# untitled.net
KiCad netlist of a schematic drawn in EAGLE
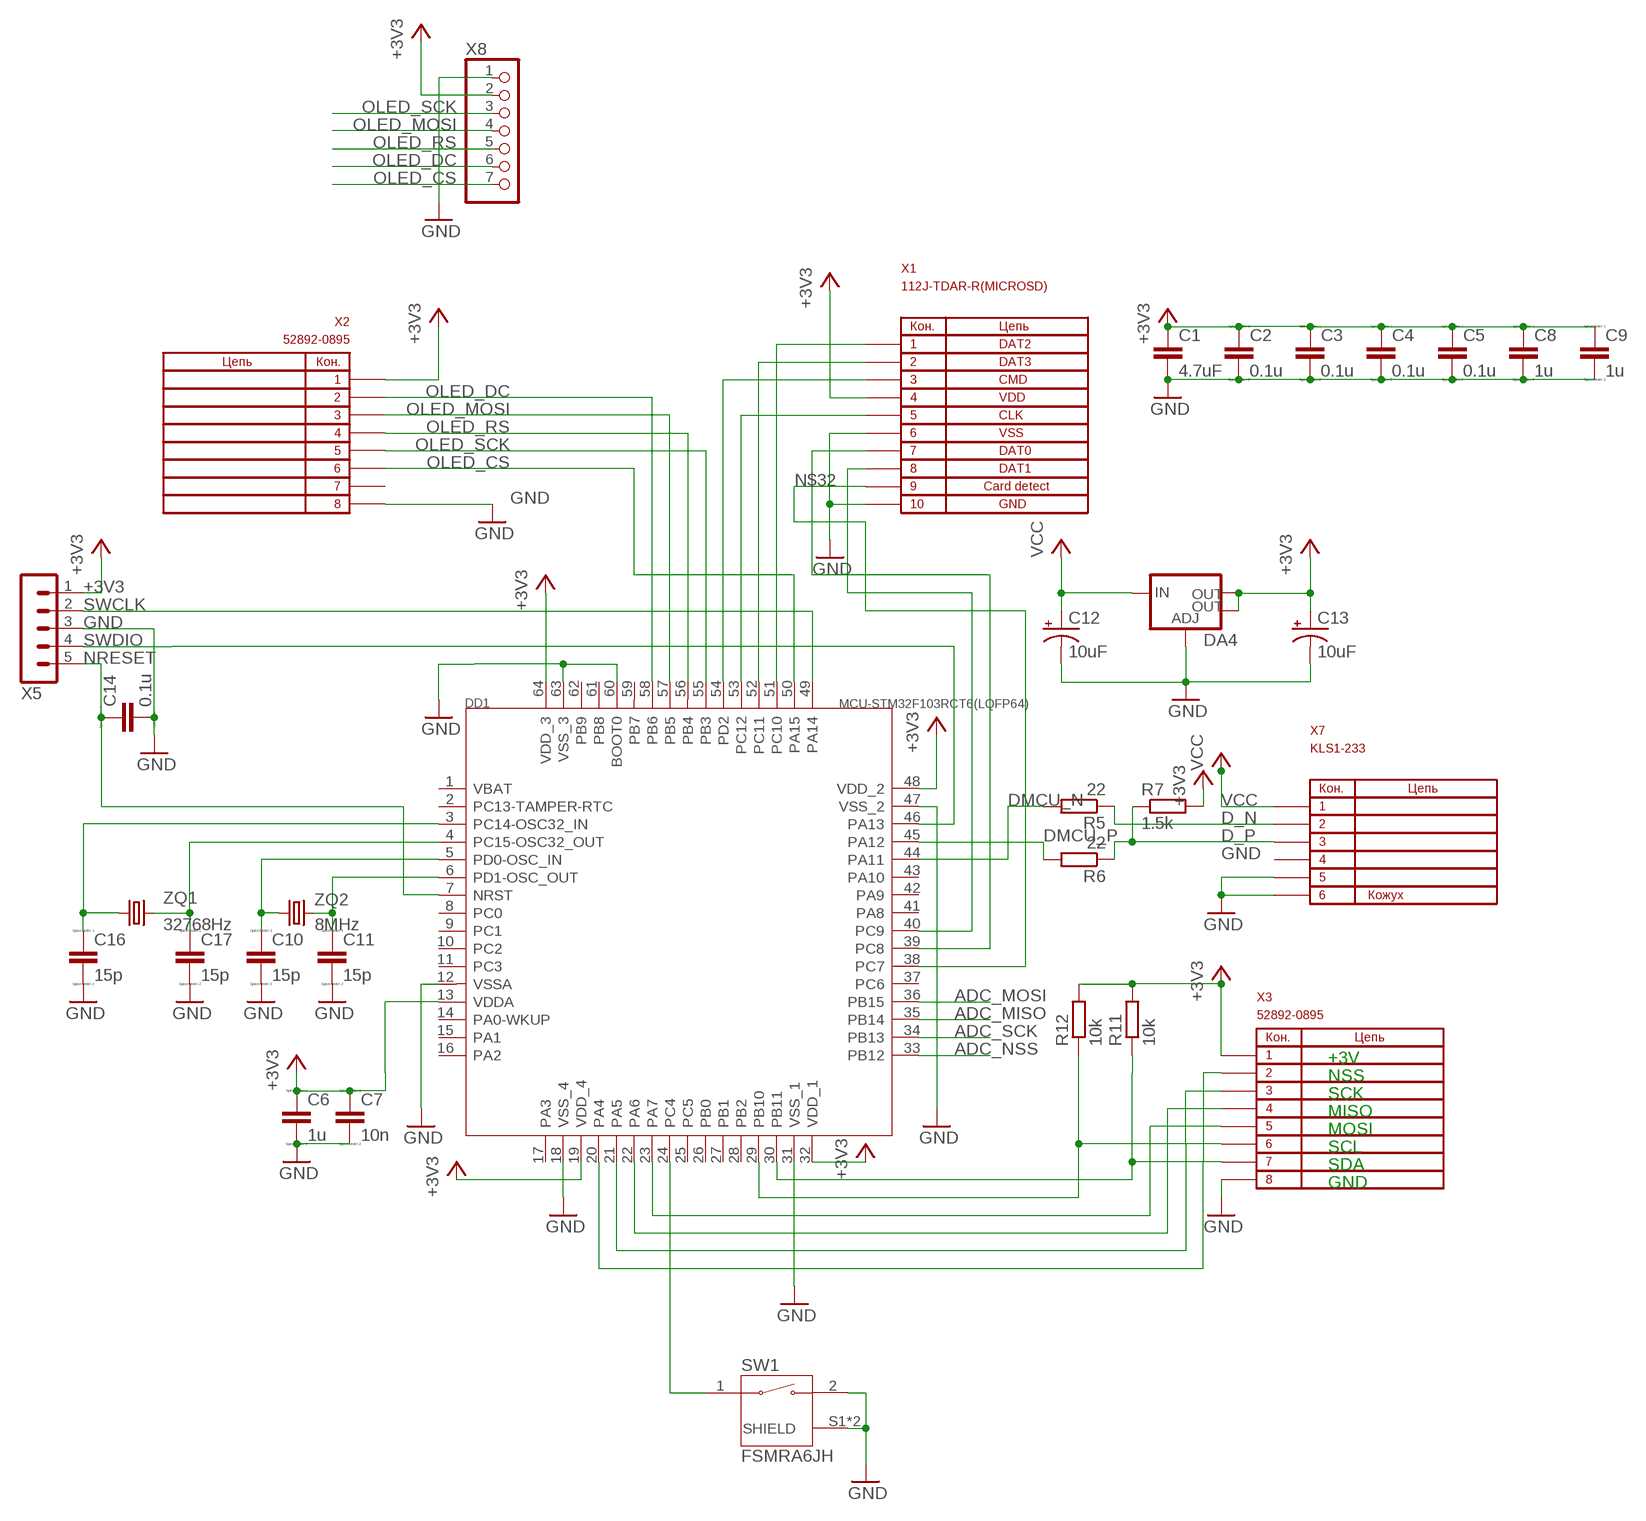
[diagram p0: schematic, sheet 1]
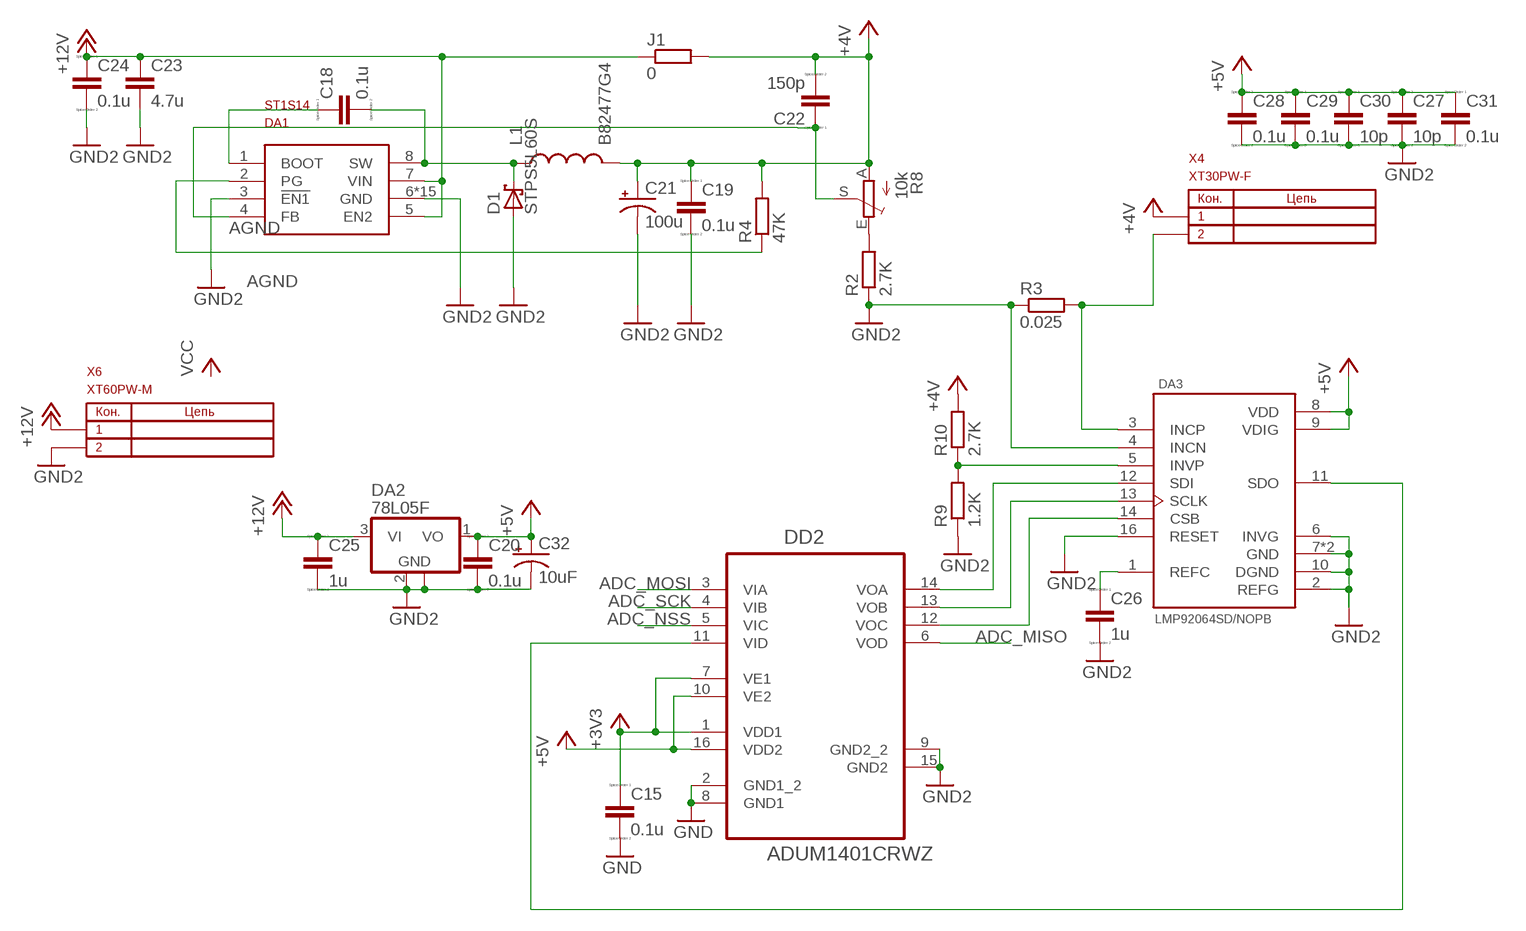
[diagram p1: schematic, sheet 2]

(export (version "E")
  (design (tool "Eeschema 10.0.6"))
  (components
    (comp (ref "C1")
      (value "4.7uF")
      (footprint "eagle-import:0603")
      (libsource (lib "eagle-import") (part "4.7UF0603"))
    )
    (comp (ref "C2")
      (value "0.1u")
      (footprint "eagle-import:C0603")
      (libsource (lib "eagle-import") (part "CC0603"))
    )
    (comp (ref "C3")
      (value "0.1u")
      (footprint "eagle-import:C0603")
      (libsource (lib "eagle-import") (part "CC0603"))
    )
    (comp (ref "C4")
      (value "0.1u")
      (footprint "eagle-import:C0603")
      (libsource (lib "eagle-import") (part "CC0603"))
    )
    (comp (ref "C5")
      (value "0.1u")
      (footprint "eagle-import:C0603")
      (libsource (lib "eagle-import") (part "CC0603"))
    )
    (comp (ref "C6")
      (value "1u")
      (footprint "eagle-import:C0603")
      (libsource (lib "eagle-import") (part "CC0603"))
    )
    (comp (ref "C7")
      (value "10n")
      (footprint "eagle-import:C0603")
      (libsource (lib "eagle-import") (part "CC0603"))
    )
    (comp (ref "C8")
      (value "1u")
      (footprint "eagle-import:C0603")
      (libsource (lib "eagle-import") (part "CC0603"))
    )
    (comp (ref "C9")
      (value "1u")
      (footprint "eagle-import:C0603")
      (libsource (lib "eagle-import") (part "CC0603"))
    )
    (comp (ref "C10")
      (value "15p")
      (footprint "eagle-import:C0603")
      (libsource (lib "eagle-import") (part "CC0603"))
    )
    (comp (ref "C11")
      (value "15p")
      (footprint "eagle-import:C0603")
      (libsource (lib "eagle-import") (part "CC0603"))
    )
    (comp (ref "C12")
      (value "10uF")
      (footprint "eagle-import:EIA3216")
      (libsource (lib "eagle-import") (part "10UF-POLAR-EIA3216-16V-10%(TANT)"))
    )
    (comp (ref "C13")
      (value "10uF")
      (footprint "eagle-import:EIA3216")
      (libsource (lib "eagle-import") (part "10UF-POLAR-EIA3216-16V-10%(TANT)"))
    )
    (comp (ref "C14")
      (value "0.1u")
      (footprint "eagle-import:C0603")
      (libsource (lib "eagle-import") (part "CC0603"))
    )
    (comp (ref "C16")
      (value "15p")
      (footprint "eagle-import:C0603")
      (libsource (lib "eagle-import") (part "CC0603"))
    )
    (comp (ref "C17")
      (value "15p")
      (footprint "eagle-import:C0603")
      (libsource (lib "eagle-import") (part "CC0603"))
    )
    (comp (ref "DA4")
      (value "V_REG_LM1117SOT223")
      (footprint "eagle-import:SOT223")
      (libsource (lib "eagle-import") (part "V_REG_LM1117SOT223"))
    )
    (comp (ref "DD1")
      (value "MCU-STM32F103RCT6(LQFP64)")
      (footprint "eagle-import:LQFP64-0.5-10X10MM")
      (fields (field (name "MF") "STMicroelectronics") (field (name "MP") "STM32F103RCT6"))
      (libsource (lib "eagle-import") (part "MCU-STM32F103RCT6(LQFP64)"))
    )
    (comp (ref "R5")
      (value "22")
      (footprint "eagle-import:R0603")
      (libsource (lib "eagle-import") (part "resistor_348_R-EU_R0603"))
    )
    (comp (ref "R6")
      (value "22")
      (footprint "eagle-import:R0603")
      (libsource (lib "eagle-import") (part "resistor_348_R-EU_R0603"))
    )
    (comp (ref "R7")
      (value "1.5k")
      (footprint "eagle-import:R0603")
      (libsource (lib "eagle-import") (part "resistor_348_R-EU_R0603"))
    )
    (comp (ref "R11")
      (value "10k")
      (footprint "eagle-import:R0603")
      (libsource (lib "eagle-import") (part "resistor_348_R-EU_R0603"))
    )
    (comp (ref "R12")
      (value "10k")
      (footprint "eagle-import:R0603")
      (libsource (lib "eagle-import") (part "resistor_348_R-EU_R0603"))
    )
    (comp (ref "SW1")
      (value "FSMRA6JH")
      (footprint "eagle-import:TE_FSMRA6JH")
      (fields (field (name "MF") "TE Connectivity"))
      (libsource (lib "eagle-import") (part "FSMRA6JH"))
    )
    (comp (ref "X1")
      (value "112J-TDAR-R(MICROSD)")
      (footprint "eagle-import:112J-TDAR-R")
      (libsource (lib "eagle-import") (part "112J-TDAR-R(MICROSD)"))
    )
    (comp (ref "X2")
      (value "52892-0895")
      (footprint "eagle-import:MOLEX_52892-0895")
      (fields (field (name "MF") "Molex"))
      (libsource (lib "eagle-import") (part "52892-0895"))
    )
    (comp (ref "X3")
      (value "52892-0895")
      (footprint "eagle-import:MOLEX_52892-0895")
      (fields (field (name "MF") "Molex"))
      (libsource (lib "eagle-import") (part "52892-0895"))
    )
    (comp (ref "X5")
      (value "MA05-1")
      (footprint "eagle-import:MA05-1")
      (libsource (lib "eagle-import") (part "MA05-1"))
    )
    (comp (ref "X7")
      (value "KLS1-233")
      (footprint "eagle-import:KLS1-233")
      (libsource (lib "eagle-import") (part "KLS1-233"))
    )
    (comp (ref "X8")
      (value "PINHD-1X7")
      (footprint "eagle-import:1X07")
      (libsource (lib "eagle-import") (part "PINHD-1X7"))
    )
    (comp (ref "ZQ1")
      (value "32768Hz")
      (footprint "eagle-import:3.2X1.5")
      (libsource (lib "eagle-import") (part "KX-327-NHT"))
    )
    (comp (ref "ZQ2")
      (value "8MHz")
      (footprint "eagle-import:HC49UP")
      (libsource (lib "eagle-import") (part "CRYSTALHC49UP"))
    )
    (comp (ref "C15")
      (value "0.1u")
      (footprint "eagle-import:C0603")
      (libsource (lib "eagle-import") (part "CC0603"))
    )
    (comp (ref "C18")
      (value "0.1u")
      (footprint "eagle-import:C0603")
      (libsource (lib "eagle-import") (part "CC0603"))
    )
    (comp (ref "C19")
      (value "0.1u")
      (footprint "eagle-import:C0603")
      (libsource (lib "eagle-import") (part "CC0603"))
    )
    (comp (ref "C20")
      (value "0.1u")
      (footprint "eagle-import:C0603")
      (libsource (lib "eagle-import") (part "CC0603"))
    )
    (comp (ref "C21")
      (value "100u")
      (footprint "eagle-import:150CLZ-1014")
      (libsource (lib "eagle-import") (part "CPOL-US150CLZ-1014"))
    )
    (comp (ref "C22")
      (value "150p")
      (footprint "eagle-import:C0603")
      (libsource (lib "eagle-import") (part "CC0603"))
    )
    (comp (ref "C23")
      (value "4.7u")
      (footprint "eagle-import:C2220K")
      (libsource (lib "eagle-import") (part "C-EUC2220K"))
    )
    (comp (ref "C24")
      (value "0.1u")
      (footprint "eagle-import:C0603")
      (libsource (lib "eagle-import") (part "CC0603"))
    )
    (comp (ref "C25")
      (value "1u")
      (footprint "eagle-import:C1206")
      (libsource (lib "eagle-import") (part "CC1206"))
    )
    (comp (ref "C26")
      (value "1u")
      (footprint "eagle-import:C0603")
      (libsource (lib "eagle-import") (part "CC0603"))
    )
    (comp (ref "C27")
      (value "10p")
      (footprint "eagle-import:C0603")
      (libsource (lib "eagle-import") (part "CC0603"))
    )
    (comp (ref "C28")
      (value "0.1u")
      (footprint "eagle-import:C0603")
      (libsource (lib "eagle-import") (part "CC0603"))
    )
    (comp (ref "C29")
      (value "0.1u")
      (footprint "eagle-import:C0603")
      (libsource (lib "eagle-import") (part "CC0603"))
    )
    (comp (ref "C30")
      (value "10p")
      (footprint "eagle-import:C0603")
      (libsource (lib "eagle-import") (part "CC0603"))
    )
    (comp (ref "C31")
      (value "0.1u")
      (footprint "eagle-import:C0603")
      (libsource (lib "eagle-import") (part "CC0603"))
    )
    (comp (ref "C32")
      (value "10uF")
      (footprint "eagle-import:EIA3216")
      (libsource (lib "eagle-import") (part "10UF-POLAR-EIA3216-16V-10%(TANT)"))
    )
    (comp (ref "D1")
      (value "STPS5L60S")
      (footprint "eagle-import:SMC")
      (libsource (lib "eagle-import") (part "STPS5L60S"))
    )
    (comp (ref "DA1")
      (value "ST1S14")
      (footprint "eagle-import:HSOP8")
      (libsource (lib "eagle-import") (part "ST1S14"))
    )
    (comp (ref "DA2")
      (value "78L05F")
      (footprint "eagle-import:SOT89")
      (libsource (lib "eagle-import") (part "78LF05"))
    )
    (comp (ref "DA3")
      (value "LMP92064SD/NOPB")
      (footprint "eagle-import:SON50P400X500X80-17N")
      (fields (field (name "MF") "Texas Instruments"))
      (libsource (lib "eagle-import") (part "LMP92064SD/NOPB"))
    )
    (comp (ref "DD2")
      (value "ADUM1401CRWZ")
      (footprint "eagle-import:SO-16W")
      (fields (field (name "MF") "Analog Devices"))
      (libsource (lib "eagle-import") (part "ADUM1401CRWZ"))
    )
    (comp (ref "J1")
      (value "0")
      (footprint "eagle-import:R2010")
      (libsource (lib "eagle-import") (part "R-EU_R2010"))
    )
    (comp (ref "L1")
      (value "B82477G4")
      (footprint "eagle-import:B82477G4")
      (libsource (lib "eagle-import") (part "B82477G4"))
    )
    (comp (ref "R2")
      (value "2.7K")
      (footprint "eagle-import:R0603")
      (libsource (lib "eagle-import") (part "resistor_348_R-EU_R0603"))
    )
    (comp (ref "R3")
      (value "0.025")
      (footprint "eagle-import:R2010")
      (libsource (lib "eagle-import") (part "R-EU_R2010"))
    )
    (comp (ref "R4")
      (value "47K")
      (footprint "eagle-import:R0603")
      (libsource (lib "eagle-import") (part "resistor_348_R-EU_R0603"))
    )
    (comp (ref "R8")
      (value "10k")
      (footprint "eagle-import:CA6V")
      (libsource (lib "eagle-import") (part "TRIM_EU-CA6V"))
    )
    (comp (ref "R9")
      (value "1.2K")
      (footprint "eagle-import:R0603")
      (libsource (lib "eagle-import") (part "resistor_348_R-EU_R0603"))
    )
    (comp (ref "R10")
      (value "2.7K")
      (footprint "eagle-import:R0603")
      (libsource (lib "eagle-import") (part "resistor_348_R-EU_R0603"))
    )
    (comp (ref "X4")
      (value "XT30PW-F")
      (footprint "eagle-import:XT30PW-F")
      (libsource (lib "eagle-import") (part "XT30PW-F"))
    )
    (comp (ref "X6")
      (value "XT60PW-M")
      (footprint "eagle-import:XT60PW-M")
      (libsource (lib "eagle-import") (part "XT60PW-M"))
    )
  )
  (nets
    (net (code "1") (name "+3V3") (class "Default")
      (node (ref "C1") (pin "1") (pinfunction "1_1") (pintype "passive"))
      (node (ref "C13") (pin "+") (pinfunction "+_+") (pintype "passive"))
      (node (ref "C15") (pin "1") (pinfunction "1_1") (pintype "passive"))
      (node (ref "C2") (pin "1") (pinfunction "1_1") (pintype "passive"))
      (node (ref "C3") (pin "1") (pinfunction "1_1") (pintype "passive"))
      (node (ref "C4") (pin "1") (pinfunction "1_1") (pintype "passive"))
      (node (ref "C5") (pin "1") (pinfunction "1_1") (pintype "passive"))
      (node (ref "C6") (pin "1") (pinfunction "1_1") (pintype "passive"))
      (node (ref "C7") (pin "1") (pinfunction "1_1") (pintype "passive"))
      (node (ref "C8") (pin "1") (pinfunction "1_1") (pintype "passive"))
      (node (ref "C9") (pin "1") (pinfunction "1_1") (pintype "passive"))
      (node (ref "DA4") (pin "2") (pinfunction "OUT_2") (pintype "output"))
      (node (ref "DA4") (pin "4") (pinfunction "OUT_4") (pintype "output"))
      (node (ref "DD1") (pin "13") (pinfunction "VDDA_13") (pintype "bidirectional"))
      (node (ref "DD1") (pin "19") (pinfunction "VDD_4_19") (pintype "bidirectional"))
      (node (ref "DD1") (pin "32") (pinfunction "VDD_1_32") (pintype "bidirectional"))
      (node (ref "DD1") (pin "48") (pinfunction "VDD_2_48") (pintype "bidirectional"))
      (node (ref "DD1") (pin "64") (pinfunction "VDD_3_64") (pintype "bidirectional"))
      (node (ref "DD2") (pin "1") (pinfunction "VDD1_1") (pintype "power_in"))
      (node (ref "DD2") (pin "7") (pinfunction "VE1_7") (pintype "passive"))
      (node (ref "R11") (pin "2") (pinfunction "2_2") (pintype "passive"))
      (node (ref "R12") (pin "2") (pinfunction "2_2") (pintype "passive"))
      (node (ref "R7") (pin "2") (pinfunction "2_2") (pintype "passive"))
      (node (ref "X1") (pin "P$4") (pinfunction "P$4_P$4") (pintype "bidirectional"))
      (node (ref "X2") (pin "1") (pinfunction "P$1_1") (pintype "bidirectional"))
      (node (ref "X3") (pin "1") (pinfunction "P$1_1") (pintype "bidirectional"))
      (node (ref "X5") (pin "1") (pinfunction "1_1") (pintype "passive"))
      (node (ref "X8") (pin "2") (pinfunction "2_2") (pintype "passive"))
    )
    (net (code "2") (name "+4V") (class "Default")
      (node (ref "C19") (pin "1") (pinfunction "1_1") (pintype "passive"))
      (node (ref "C21") (pin "+") (pinfunction "+_+") (pintype "passive"))
      (node (ref "C22") (pin "2") (pinfunction "2_2") (pintype "passive"))
      (node (ref "J1") (pin "2") (pinfunction "2_2") (pintype "passive"))
      (node (ref "L1") (pin "P$2") (pinfunction "2_P$2") (pintype "passive"))
      (node (ref "R10") (pin "2") (pinfunction "2_2") (pintype "passive"))
      (node (ref "R4") (pin "2") (pinfunction "2_2") (pintype "passive"))
      (node (ref "R8") (pin "A") (pinfunction "A_A") (pintype "passive"))
      (node (ref "X4") (pin "P$2") (pinfunction "P$1_P$2") (pintype "bidirectional"))
    )
    (net (code "3") (name "+5V") (class "Default")
      (node (ref "C20") (pin "1") (pinfunction "1_1") (pintype "passive"))
      (node (ref "C27") (pin "1") (pinfunction "1_1") (pintype "passive"))
      (node (ref "C28") (pin "1") (pinfunction "1_1") (pintype "passive"))
      (node (ref "C29") (pin "1") (pinfunction "1_1") (pintype "passive"))
      (node (ref "C30") (pin "1") (pinfunction "1_1") (pintype "passive"))
      (node (ref "C31") (pin "1") (pinfunction "1_1") (pintype "passive"))
      (node (ref "C32") (pin "+") (pinfunction "+_+") (pintype "passive"))
      (node (ref "DA2") (pin "1") (pinfunction "VO_1") (pintype "passive"))
      (node (ref "DA3") (pin "8") (pinfunction "VDD_8") (pintype "power_in"))
      (node (ref "DA3") (pin "9") (pinfunction "VDIG_9") (pintype "power_in"))
      (node (ref "DD2") (pin "10") (pinfunction "VE2_10") (pintype "passive"))
      (node (ref "DD2") (pin "16") (pinfunction "VDD2_16") (pintype "power_in"))
    )
    (net (code "4") (name "+12V") (class "Default")
      (node (ref "C23") (pin "1") (pinfunction "1_1") (pintype "passive"))
      (node (ref "C24") (pin "1") (pinfunction "1_1") (pintype "passive"))
      (node (ref "C25") (pin "1") (pinfunction "1_1") (pintype "passive"))
      (node (ref "DA1") (pin "5") (pinfunction "EN2_5") (pintype "bidirectional"))
      (node (ref "DA1") (pin "7") (pinfunction "VIN_7") (pintype "bidirectional"))
      (node (ref "DA2") (pin "3") (pinfunction "VI_3") (pintype "input"))
      (node (ref "J1") (pin "1") (pinfunction "1_1") (pintype "passive"))
      (node (ref "X6") (pin "P$2") (pinfunction "P$1_P$2") (pintype "bidirectional"))
    )
    (net (code "5") (name "ADC_MISO") (class "Default")
      (node (ref "DD1") (pin "35") (pinfunction "PB14_35") (pintype "bidirectional"))
      (node (ref "DD2") (pin "6") (pinfunction "VOD_6") (pintype "passive"))
    )
    (net (code "6") (name "ADC_MOSI") (class "Default")
      (node (ref "DD1") (pin "36") (pinfunction "PB15_36") (pintype "bidirectional"))
      (node (ref "DD2") (pin "3") (pinfunction "VIA_3") (pintype "passive"))
    )
    (net (code "7") (name "ADC_NSS") (class "Default")
      (node (ref "DD1") (pin "33") (pinfunction "PB12_33") (pintype "bidirectional"))
      (node (ref "DD2") (pin "5") (pinfunction "VIC_5") (pintype "passive"))
    )
    (net (code "8") (name "ADC_SCK") (class "Default")
      (node (ref "DD1") (pin "34") (pinfunction "PB13_34") (pintype "bidirectional"))
      (node (ref "DD2") (pin "4") (pinfunction "VIB_4") (pintype "passive"))
    )
    (net (code "9") (name "AGND") (class "Default")
      (node (ref "C19") (pin "2") (pinfunction "2_2") (pintype "passive"))
      (node (ref "C20") (pin "2") (pinfunction "2_2") (pintype "passive"))
      (node (ref "C21") (pin "-") (pinfunction "-_-") (pintype "passive"))
      (node (ref "C23") (pin "2") (pinfunction "2_2") (pintype "passive"))
      (node (ref "C24") (pin "2") (pinfunction "2_2") (pintype "passive"))
      (node (ref "C25") (pin "2") (pinfunction "2_2") (pintype "passive"))
      (node (ref "C26") (pin "2") (pinfunction "2_2") (pintype "passive"))
      (node (ref "C27") (pin "2") (pinfunction "2_2") (pintype "passive"))
      (node (ref "C28") (pin "2") (pinfunction "2_2") (pintype "passive"))
      (node (ref "C29") (pin "2") (pinfunction "2_2") (pintype "passive"))
      (node (ref "C30") (pin "2") (pinfunction "2_2") (pintype "passive"))
      (node (ref "C31") (pin "2") (pinfunction "2_2") (pintype "passive"))
      (node (ref "C32") (pin "-") (pinfunction "-_-") (pintype "passive"))
      (node (ref "D1") (pin "A") (pinfunction "A_A") (pintype "passive"))
      (node (ref "DA1") (pin "3") (pinfunction "~{EN1}_3") (pintype "bidirectional"))
      (node (ref "DA1") (pin "6") (pinfunction "GND_6") (pintype "bidirectional"))
      (node (ref "DA1") (pin "P$10") (pinfunction "GND_P$10") (pintype "bidirectional"))
      (node (ref "DA1") (pin "P$11") (pinfunction "GND_P$11") (pintype "bidirectional"))
      (node (ref "DA1") (pin "P$12") (pinfunction "GND_P$12") (pintype "bidirectional"))
      (node (ref "DA1") (pin "P$13") (pinfunction "GND_P$13") (pintype "bidirectional"))
      (node (ref "DA1") (pin "P$14") (pinfunction "GND_P$14") (pintype "bidirectional"))
      (node (ref "DA1") (pin "P$15") (pinfunction "GND_P$15") (pintype "bidirectional"))
      (node (ref "DA1") (pin "P$16") (pinfunction "GND_P$16") (pintype "bidirectional"))
      (node (ref "DA1") (pin "P$17") (pinfunction "GND_P$17") (pintype "bidirectional"))
      (node (ref "DA1") (pin "P$18") (pinfunction "GND_P$18") (pintype "bidirectional"))
      (node (ref "DA1") (pin "P$19") (pinfunction "GND_P$19") (pintype "bidirectional"))
      (node (ref "DA1") (pin "P$20") (pinfunction "GND_P$20") (pintype "bidirectional"))
      (node (ref "DA1") (pin "P$21") (pinfunction "GND_P$21") (pintype "bidirectional"))
      (node (ref "DA1") (pin "P$22") (pinfunction "GND_P$22") (pintype "bidirectional"))
      (node (ref "DA1") (pin "P$9") (pinfunction "GND_P$9") (pintype "bidirectional"))
      (node (ref "DA2") (pin "2") (pinfunction "GND_2") (pintype "passive"))
      (node (ref "DA2") (pin "2@1") (pinfunction "GND_2@1") (pintype "passive"))
      (node (ref "DA3") (pin "10") (pinfunction "DGND_10") (pintype "power_in"))
      (node (ref "DA3") (pin "16") (pinfunction "RESET_16") (pintype "input"))
      (node (ref "DA3") (pin "17") (pinfunction "GND_17") (pintype "power_in"))
      (node (ref "DA3") (pin "2") (pinfunction "REFG_2") (pintype "power_in"))
      (node (ref "DA3") (pin "4") (pinfunction "INCN_4") (pintype "input"))
      (node (ref "DA3") (pin "6") (pinfunction "INVG_6") (pintype "power_in"))
      (node (ref "DA3") (pin "7") (pinfunction "GND_7") (pintype "power_in"))
      (node (ref "DD2") (pin "15") (pinfunction "GND2_15") (pintype "passive"))
      (node (ref "DD2") (pin "9") (pinfunction "GND2_2_9") (pintype "passive"))
      (node (ref "R2") (pin "1") (pinfunction "1_1") (pintype "passive"))
      (node (ref "R3") (pin "1") (pinfunction "1_1") (pintype "passive"))
      (node (ref "R9") (pin "1") (pinfunction "1_1") (pintype "passive"))
      (node (ref "X6") (pin "P$1") (pinfunction "P$2_P$1") (pintype "bidirectional"))
    )
    (net (code "10") (name "DMCU_N") (class "Default")
      (node (ref "DD1") (pin "44") (pinfunction "PA11_44") (pintype "bidirectional"))
      (node (ref "R5") (pin "2") (pinfunction "2_2") (pintype "passive"))
    )
    (net (code "11") (name "DMCU_P") (class "Default")
      (node (ref "DD1") (pin "45") (pinfunction "PA12_45") (pintype "bidirectional"))
      (node (ref "R6") (pin "2") (pinfunction "2_2") (pintype "passive"))
    )
    (net (code "12") (name "D_N") (class "Default")
      (node (ref "R5") (pin "1") (pinfunction "1_1") (pintype "passive"))
      (node (ref "X7") (pin "2") (pinfunction "P$2_2") (pintype "bidirectional"))
    )
    (net (code "13") (name "D_P") (class "Default")
      (node (ref "R6") (pin "1") (pinfunction "1_1") (pintype "passive"))
      (node (ref "R7") (pin "1") (pinfunction "1_1") (pintype "passive"))
      (node (ref "X7") (pin "3") (pinfunction "P$3_3") (pintype "bidirectional"))
    )
    (net (code "14") (name "GND") (class "Default")
      (node (ref "C1") (pin "2") (pinfunction "2_2") (pintype "passive"))
      (node (ref "C10") (pin "2") (pinfunction "2_2") (pintype "passive"))
      (node (ref "C11") (pin "2") (pinfunction "2_2") (pintype "passive"))
      (node (ref "C12") (pin "-") (pinfunction "-_-") (pintype "passive"))
      (node (ref "C13") (pin "-") (pinfunction "-_-") (pintype "passive"))
      (node (ref "C14") (pin "2") (pinfunction "2_2") (pintype "passive"))
      (node (ref "C15") (pin "2") (pinfunction "2_2") (pintype "passive"))
      (node (ref "C16") (pin "2") (pinfunction "2_2") (pintype "passive"))
      (node (ref "C17") (pin "2") (pinfunction "2_2") (pintype "passive"))
      (node (ref "C2") (pin "2") (pinfunction "2_2") (pintype "passive"))
      (node (ref "C3") (pin "2") (pinfunction "2_2") (pintype "passive"))
      (node (ref "C4") (pin "2") (pinfunction "2_2") (pintype "passive"))
      (node (ref "C5") (pin "2") (pinfunction "2_2") (pintype "passive"))
      (node (ref "C6") (pin "2") (pinfunction "2_2") (pintype "passive"))
      (node (ref "C7") (pin "2") (pinfunction "2_2") (pintype "passive"))
      (node (ref "C8") (pin "2") (pinfunction "2_2") (pintype "passive"))
      (node (ref "C9") (pin "2") (pinfunction "2_2") (pintype "passive"))
      (node (ref "DA4") (pin "1") (pinfunction "ADJ_1") (pintype "input"))
      (node (ref "DD1") (pin "12") (pinfunction "VSSA_12") (pintype "bidirectional"))
      (node (ref "DD1") (pin "18") (pinfunction "VSS_4_18") (pintype "bidirectional"))
      (node (ref "DD1") (pin "31") (pinfunction "VSS_1_31") (pintype "bidirectional"))
      (node (ref "DD1") (pin "47") (pinfunction "VSS_2_47") (pintype "bidirectional"))
      (node (ref "DD1") (pin "60") (pinfunction "BOOT0_60") (pintype "bidirectional"))
      (node (ref "DD1") (pin "63") (pinfunction "VSS_3_63") (pintype "bidirectional"))
      (node (ref "DD2") (pin "2") (pinfunction "GND1_2_2") (pintype "passive"))
      (node (ref "DD2") (pin "8") (pinfunction "GND1_8") (pintype "passive"))
      (node (ref "SW1") (pin "2") (pinfunction "2_2") (pintype "passive"))
      (node (ref "SW1") (pin "S1") (pinfunction "SHIELD_S1") (pintype "passive"))
      (node (ref "SW1") (pin "S2") (pinfunction "SHIELD_S2") (pintype "passive"))
      (node (ref "X1") (pin "P$10") (pinfunction "P$10_P$10") (pintype "bidirectional"))
      (node (ref "X1") (pin "P$11") (pinfunction "P$10_P$11") (pintype "bidirectional"))
      (node (ref "X1") (pin "P$12") (pinfunction "P$10_P$12") (pintype "bidirectional"))
      (node (ref "X1") (pin "P$13") (pinfunction "P$10_P$13") (pintype "bidirectional"))
      (node (ref "X1") (pin "P$6") (pinfunction "P$6_P$6") (pintype "bidirectional"))
      (node (ref "X2") (pin "8") (pinfunction "P$8_8") (pintype "bidirectional"))
      (node (ref "X3") (pin "8") (pinfunction "P$8_8") (pintype "bidirectional"))
      (node (ref "X5") (pin "3") (pinfunction "3_3") (pintype "passive"))
      (node (ref "X7") (pin "5") (pinfunction "P$5_5") (pintype "bidirectional"))
      (node (ref "X7") (pin "SH4") (pinfunction "P$6_SH4") (pintype "bidirectional"))
      (node (ref "X7") (pin "SH5") (pinfunction "P$6_SH5") (pintype "bidirectional"))
      (node (ref "X7") (pin "SH6") (pinfunction "P$6_SH6") (pintype "bidirectional"))
      (node (ref "X7") (pin "SH7") (pinfunction "P$6_SH7") (pintype "bidirectional"))
      (node (ref "X8") (pin "1") (pinfunction "1_1") (pintype "passive"))
    )
    (net (code "15") (name "N$32") (class "Default")
      (node (ref "DD1") (pin "38") (pinfunction "PC7_38") (pintype "bidirectional"))
      (node (ref "X1") (pin "P$9") (pinfunction "P$9_P$9") (pintype "bidirectional"))
    )
    (net (code "16") (name "NRESET") (class "Default")
      (node (ref "C14") (pin "1") (pinfunction "1_1") (pintype "passive"))
      (node (ref "DD1") (pin "7") (pinfunction "NRST_7") (pintype "bidirectional"))
      (node (ref "X5") (pin "5") (pinfunction "5_5") (pintype "passive"))
    )
    (net (code "17") (name "Net-(DA1-BOOT)") (class "Default")
      (node (ref "C18") (pin "1") (pinfunction "1_1") (pintype "passive"))
      (node (ref "DA1") (pin "1") (pinfunction "BOOT_1") (pintype "bidirectional"))
    )
    (net (code "18") (name "Net-(DA1-FB)") (class "Default")
      (node (ref "C22") (pin "1") (pinfunction "1_1") (pintype "passive"))
      (node (ref "DA1") (pin "4") (pinfunction "FB_4") (pintype "bidirectional"))
      (node (ref "R8") (pin "S") (pinfunction "S_S") (pintype "passive"))
    )
    (net (code "19") (name "Net-(DA1-PG)") (class "Default")
      (node (ref "DA1") (pin "2") (pinfunction "PG_2") (pintype "bidirectional"))
      (node (ref "R4") (pin "1") (pinfunction "1_1") (pintype "passive"))
    )
    (net (code "20") (name "Net-(DA1-SW)") (class "Default")
      (node (ref "C18") (pin "2") (pinfunction "2_2") (pintype "passive"))
      (node (ref "D1") (pin "C") (pinfunction "C_C") (pintype "passive"))
      (node (ref "DA1") (pin "8") (pinfunction "SW_8") (pintype "bidirectional"))
      (node (ref "L1") (pin "P$1") (pinfunction "1_P$1") (pintype "passive"))
    )
    (net (code "21") (name "Net-(DA3-CSB)") (class "Default")
      (node (ref "DA3") (pin "14") (pinfunction "CSB_14") (pintype "input"))
      (node (ref "DD2") (pin "12") (pinfunction "VOC_12") (pintype "passive"))
    )
    (net (code "22") (name "Net-(DA3-INCP)") (class "Default")
      (node (ref "DA3") (pin "3") (pinfunction "INCP_3") (pintype "input"))
      (node (ref "R3") (pin "2") (pinfunction "2_2") (pintype "passive"))
      (node (ref "X4") (pin "P$1") (pinfunction "P$2_P$1") (pintype "bidirectional"))
    )
    (net (code "23") (name "Net-(DA3-INVP)") (class "Default")
      (node (ref "DA3") (pin "5") (pinfunction "INVP_5") (pintype "input"))
      (node (ref "R10") (pin "1") (pinfunction "1_1") (pintype "passive"))
      (node (ref "R9") (pin "2") (pinfunction "2_2") (pintype "passive"))
    )
    (net (code "24") (name "Net-(DA3-REFC)") (class "Default")
      (node (ref "C26") (pin "1") (pinfunction "1_1") (pintype "passive"))
      (node (ref "DA3") (pin "1") (pinfunction "REFC_1") (pintype "passive"))
    )
    (net (code "25") (name "Net-(DA3-SCLK)") (class "Default")
      (node (ref "DA3") (pin "13") (pinfunction "SCLK_13") (pintype "input"))
      (node (ref "DD2") (pin "13") (pinfunction "VOB_13") (pintype "passive"))
    )
    (net (code "26") (name "Net-(DA3-SDI)") (class "Default")
      (node (ref "DA3") (pin "12") (pinfunction "SDI_12") (pintype "input"))
      (node (ref "DD2") (pin "14") (pinfunction "VOA_14") (pintype "passive"))
    )
    (net (code "27") (name "Net-(DA3-SDO)") (class "Default")
      (node (ref "DA3") (pin "11") (pinfunction "SDO_11") (pintype "output"))
      (node (ref "DD2") (pin "11") (pinfunction "VID_11") (pintype "passive"))
    )
    (net (code "28") (name "Net-(DD1-PA4)") (class "Default")
      (node (ref "DD1") (pin "20") (pinfunction "PA4_20") (pintype "bidirectional"))
      (node (ref "X3") (pin "2") (pinfunction "P$2_2") (pintype "bidirectional"))
    )
    (net (code "29") (name "Net-(DD1-PA5)") (class "Default")
      (node (ref "DD1") (pin "21") (pinfunction "PA5_21") (pintype "bidirectional"))
      (node (ref "X3") (pin "3") (pinfunction "P$3_3") (pintype "bidirectional"))
    )
    (net (code "30") (name "Net-(DD1-PA6)") (class "Default")
      (node (ref "DD1") (pin "22") (pinfunction "PA6_22") (pintype "bidirectional"))
      (node (ref "X3") (pin "4") (pinfunction "P$4_4") (pintype "bidirectional"))
    )
    (net (code "31") (name "Net-(DD1-PA7)") (class "Default")
      (node (ref "DD1") (pin "23") (pinfunction "PA7_23") (pintype "bidirectional"))
      (node (ref "X3") (pin "5") (pinfunction "P$5_5") (pintype "bidirectional"))
    )
    (net (code "32") (name "Net-(DD1-PB10)") (class "Default")
      (node (ref "DD1") (pin "29") (pinfunction "PB10_29") (pintype "bidirectional"))
      (node (ref "R12") (pin "1") (pinfunction "1_1") (pintype "passive"))
      (node (ref "X3") (pin "6") (pinfunction "P$6_6") (pintype "bidirectional"))
    )
    (net (code "33") (name "Net-(DD1-PB11)") (class "Default")
      (node (ref "DD1") (pin "30") (pinfunction "PB11_30") (pintype "bidirectional"))
      (node (ref "R11") (pin "1") (pinfunction "1_1") (pintype "passive"))
      (node (ref "X3") (pin "7") (pinfunction "P$7_7") (pintype "bidirectional"))
    )
    (net (code "34") (name "Net-(DD1-PC4)") (class "Default")
      (node (ref "DD1") (pin "24") (pinfunction "PC4_24") (pintype "bidirectional"))
      (node (ref "SW1") (pin "1") (pinfunction "1_1") (pintype "passive"))
    )
    (net (code "35") (name "Net-(DD1-PC8)") (class "Default")
      (node (ref "DD1") (pin "39") (pinfunction "PC8_39") (pintype "bidirectional"))
      (node (ref "X1") (pin "P$7") (pinfunction "P$7_P$7") (pintype "bidirectional"))
    )
    (net (code "36") (name "Net-(DD1-PC9)") (class "Default")
      (node (ref "DD1") (pin "40") (pinfunction "PC9_40") (pintype "bidirectional"))
      (node (ref "X1") (pin "P$8") (pinfunction "P$8_P$8") (pintype "bidirectional"))
    )
    (net (code "37") (name "Net-(DD1-PC10)") (class "Default")
      (node (ref "DD1") (pin "51") (pinfunction "PC10_51") (pintype "bidirectional"))
      (node (ref "X1") (pin "P$1") (pinfunction "P$1_P$1") (pintype "bidirectional"))
    )
    (net (code "38") (name "Net-(DD1-PC11)") (class "Default")
      (node (ref "DD1") (pin "52") (pinfunction "PC11_52") (pintype "bidirectional"))
      (node (ref "X1") (pin "P$2") (pinfunction "P$2_P$2") (pintype "bidirectional"))
    )
    (net (code "39") (name "Net-(DD1-PC12)") (class "Default")
      (node (ref "DD1") (pin "53") (pinfunction "PC12_53") (pintype "bidirectional"))
      (node (ref "X1") (pin "P$5") (pinfunction "P$5_P$5") (pintype "bidirectional"))
    )
    (net (code "40") (name "Net-(DD1-PC14-OSC32_IN)") (class "Default")
      (node (ref "C16") (pin "1") (pinfunction "1_1") (pintype "passive"))
      (node (ref "DD1") (pin "3") (pinfunction "PC14-OSC32_IN_3") (pintype "bidirectional"))
      (node (ref "ZQ1") (pin "1") (pinfunction "1_1") (pintype "passive"))
    )
    (net (code "41") (name "Net-(DD1-PC15-OSC32_OUT)") (class "Default")
      (node (ref "C17") (pin "1") (pinfunction "1_1") (pintype "passive"))
      (node (ref "DD1") (pin "4") (pinfunction "PC15-OSC32_OUT_4") (pintype "bidirectional"))
      (node (ref "ZQ1") (pin "2") (pinfunction "2_2") (pintype "passive"))
    )
    (net (code "42") (name "Net-(DD1-PD0-OSC_IN)") (class "Default")
      (node (ref "C10") (pin "1") (pinfunction "1_1") (pintype "passive"))
      (node (ref "DD1") (pin "5") (pinfunction "PD0-OSC_IN_5") (pintype "bidirectional"))
      (node (ref "ZQ2") (pin "1") (pinfunction "1_1") (pintype "passive"))
    )
    (net (code "43") (name "Net-(DD1-PD1-OSC_OUT)") (class "Default")
      (node (ref "C11") (pin "1") (pinfunction "1_1") (pintype "passive"))
      (node (ref "DD1") (pin "6") (pinfunction "PD1-OSC_OUT_6") (pintype "bidirectional"))
      (node (ref "ZQ2") (pin "2") (pinfunction "2_2") (pintype "passive"))
    )
    (net (code "44") (name "Net-(DD1-PD2)") (class "Default")
      (node (ref "DD1") (pin "54") (pinfunction "PD2_54") (pintype "bidirectional"))
      (node (ref "X1") (pin "P$3") (pinfunction "P$3_P$3") (pintype "bidirectional"))
    )
    (net (code "45") (name "Net-(R2-Pad2)") (class "Default")
      (node (ref "R2") (pin "2") (pinfunction "2_2") (pintype "passive"))
      (node (ref "R8") (pin "E") (pinfunction "E_E") (pintype "passive"))
    )
    (net (code "46") (name "OLED_CS") (class "Default")
      (node (ref "DD1") (pin "50") (pinfunction "PA15_50") (pintype "bidirectional"))
      (node (ref "X2") (pin "6") (pinfunction "P$6_6") (pintype "bidirectional"))
      (node (ref "X8") (pin "7") (pinfunction "7_7") (pintype "passive"))
    )
    (net (code "47") (name "OLED_DC") (class "Default")
      (node (ref "DD1") (pin "58") (pinfunction "PB6_58") (pintype "bidirectional"))
      (node (ref "X2") (pin "2") (pinfunction "P$2_2") (pintype "bidirectional"))
      (node (ref "X8") (pin "6") (pinfunction "6_6") (pintype "passive"))
    )
    (net (code "48") (name "OLED_MOSI") (class "Default")
      (node (ref "DD1") (pin "57") (pinfunction "PB5_57") (pintype "bidirectional"))
      (node (ref "X2") (pin "3") (pinfunction "P$3_3") (pintype "bidirectional"))
      (node (ref "X8") (pin "4") (pinfunction "4_4") (pintype "passive"))
    )
    (net (code "49") (name "OLED_RS") (class "Default")
      (node (ref "DD1") (pin "56") (pinfunction "PB4_56") (pintype "bidirectional"))
      (node (ref "X2") (pin "4") (pinfunction "P$4_4") (pintype "bidirectional"))
      (node (ref "X8") (pin "5") (pinfunction "5_5") (pintype "passive"))
    )
    (net (code "50") (name "OLED_SCK") (class "Default")
      (node (ref "DD1") (pin "55") (pinfunction "PB3_55") (pintype "bidirectional"))
      (node (ref "X2") (pin "5") (pinfunction "P$5_5") (pintype "bidirectional"))
      (node (ref "X8") (pin "3") (pinfunction "3_3") (pintype "passive"))
    )
    (net (code "51") (name "SWCLK") (class "Default")
      (node (ref "DD1") (pin "49") (pinfunction "PA14_49") (pintype "bidirectional"))
      (node (ref "X5") (pin "2") (pinfunction "2_2") (pintype "passive"))
    )
    (net (code "52") (name "SWDIO") (class "Default")
      (node (ref "DD1") (pin "46") (pinfunction "PA13_46") (pintype "bidirectional"))
      (node (ref "X5") (pin "4") (pinfunction "4_4") (pintype "passive"))
    )
    (net (code "53") (name "VCC") (class "Default")
      (node (ref "C12") (pin "+") (pinfunction "+_+") (pintype "passive"))
      (node (ref "DA4") (pin "3") (pinfunction "IN_3") (pintype "input"))
      (node (ref "X7") (pin "1") (pinfunction "P$1_1") (pintype "bidirectional"))
    )
    (net (code "54") (name "unconnected-(DD1-PA0-WKUP-Pad14)") (class "Default")
      (node (ref "DD1") (pin "14") (pinfunction "PA0-WKUP_14") (pintype "bidirectional"))
    )
    (net (code "55") (name "unconnected-(DD1-PA1-Pad15)") (class "Default")
      (node (ref "DD1") (pin "15") (pinfunction "PA1_15") (pintype "bidirectional"))
    )
    (net (code "56") (name "unconnected-(DD1-PA2-Pad16)") (class "Default")
      (node (ref "DD1") (pin "16") (pinfunction "PA2_16") (pintype "bidirectional"))
    )
    (net (code "57") (name "unconnected-(DD1-PA3-Pad17)") (class "Default")
      (node (ref "DD1") (pin "17") (pinfunction "PA3_17") (pintype "bidirectional"))
    )
    (net (code "58") (name "unconnected-(DD1-PA8-Pad41)") (class "Default")
      (node (ref "DD1") (pin "41") (pinfunction "PA8_41") (pintype "bidirectional"))
    )
    (net (code "59") (name "unconnected-(DD1-PA9-Pad42)") (class "Default")
      (node (ref "DD1") (pin "42") (pinfunction "PA9_42") (pintype "bidirectional"))
    )
    (net (code "60") (name "unconnected-(DD1-PA10-Pad43)") (class "Default")
      (node (ref "DD1") (pin "43") (pinfunction "PA10_43") (pintype "bidirectional"))
    )
    (net (code "61") (name "unconnected-(DD1-PB0-Pad26)") (class "Default")
      (node (ref "DD1") (pin "26") (pinfunction "PB0_26") (pintype "bidirectional"))
    )
    (net (code "62") (name "unconnected-(DD1-PB1-Pad27)") (class "Default")
      (node (ref "DD1") (pin "27") (pinfunction "PB1_27") (pintype "bidirectional"))
    )
    (net (code "63") (name "unconnected-(DD1-PB2-Pad28)") (class "Default")
      (node (ref "DD1") (pin "28") (pinfunction "PB2_28") (pintype "bidirectional"))
    )
    (net (code "64") (name "unconnected-(DD1-PB7-Pad59)") (class "Default")
      (node (ref "DD1") (pin "59") (pinfunction "PB7_59") (pintype "bidirectional"))
    )
    (net (code "65") (name "unconnected-(DD1-PB8-Pad61)") (class "Default")
      (node (ref "DD1") (pin "61") (pinfunction "PB8_61") (pintype "bidirectional"))
    )
    (net (code "66") (name "unconnected-(DD1-PB9-Pad62)") (class "Default")
      (node (ref "DD1") (pin "62") (pinfunction "PB9_62") (pintype "bidirectional"))
    )
    (net (code "67") (name "unconnected-(DD1-PC0-Pad8)") (class "Default")
      (node (ref "DD1") (pin "8") (pinfunction "PC0_8") (pintype "bidirectional"))
    )
    (net (code "68") (name "unconnected-(DD1-PC1-Pad9)") (class "Default")
      (node (ref "DD1") (pin "9") (pinfunction "PC1_9") (pintype "bidirectional"))
    )
    (net (code "69") (name "unconnected-(DD1-PC2-Pad10)") (class "Default")
      (node (ref "DD1") (pin "10") (pinfunction "PC2_10") (pintype "bidirectional"))
    )
    (net (code "70") (name "unconnected-(DD1-PC3-Pad11)") (class "Default")
      (node (ref "DD1") (pin "11") (pinfunction "PC3_11") (pintype "bidirectional"))
    )
    (net (code "71") (name "unconnected-(DD1-PC5-Pad25)") (class "Default")
      (node (ref "DD1") (pin "25") (pinfunction "PC5_25") (pintype "bidirectional"))
    )
    (net (code "72") (name "unconnected-(DD1-PC6-Pad37)") (class "Default")
      (node (ref "DD1") (pin "37") (pinfunction "PC6_37") (pintype "bidirectional"))
    )
    (net (code "73") (name "unconnected-(DD1-PC13-TAMPER-RTC-Pad2)") (class "Default")
      (node (ref "DD1") (pin "2") (pinfunction "PC13-TAMPER-RTC_2") (pintype "bidirectional"))
    )
    (net (code "74") (name "unconnected-(DD1-VBAT-Pad1)") (class "Default")
      (node (ref "DD1") (pin "1") (pinfunction "VBAT_1") (pintype "bidirectional"))
    )
    (net (code "75") (name "unconnected-(X2-P$7-Pad7)") (class "Default")
      (node (ref "X2") (pin "7") (pinfunction "P$7_7") (pintype "bidirectional"))
    )
    (net (code "76") (name "unconnected-(X7-P$4-Pad4)") (class "Default")
      (node (ref "X7") (pin "4") (pinfunction "P$4_4") (pintype "bidirectional"))
    )
  )
)
